# 2_waffling60-MX_matrix.net
KiCad netlist of a schematic drawn in Altium Designer
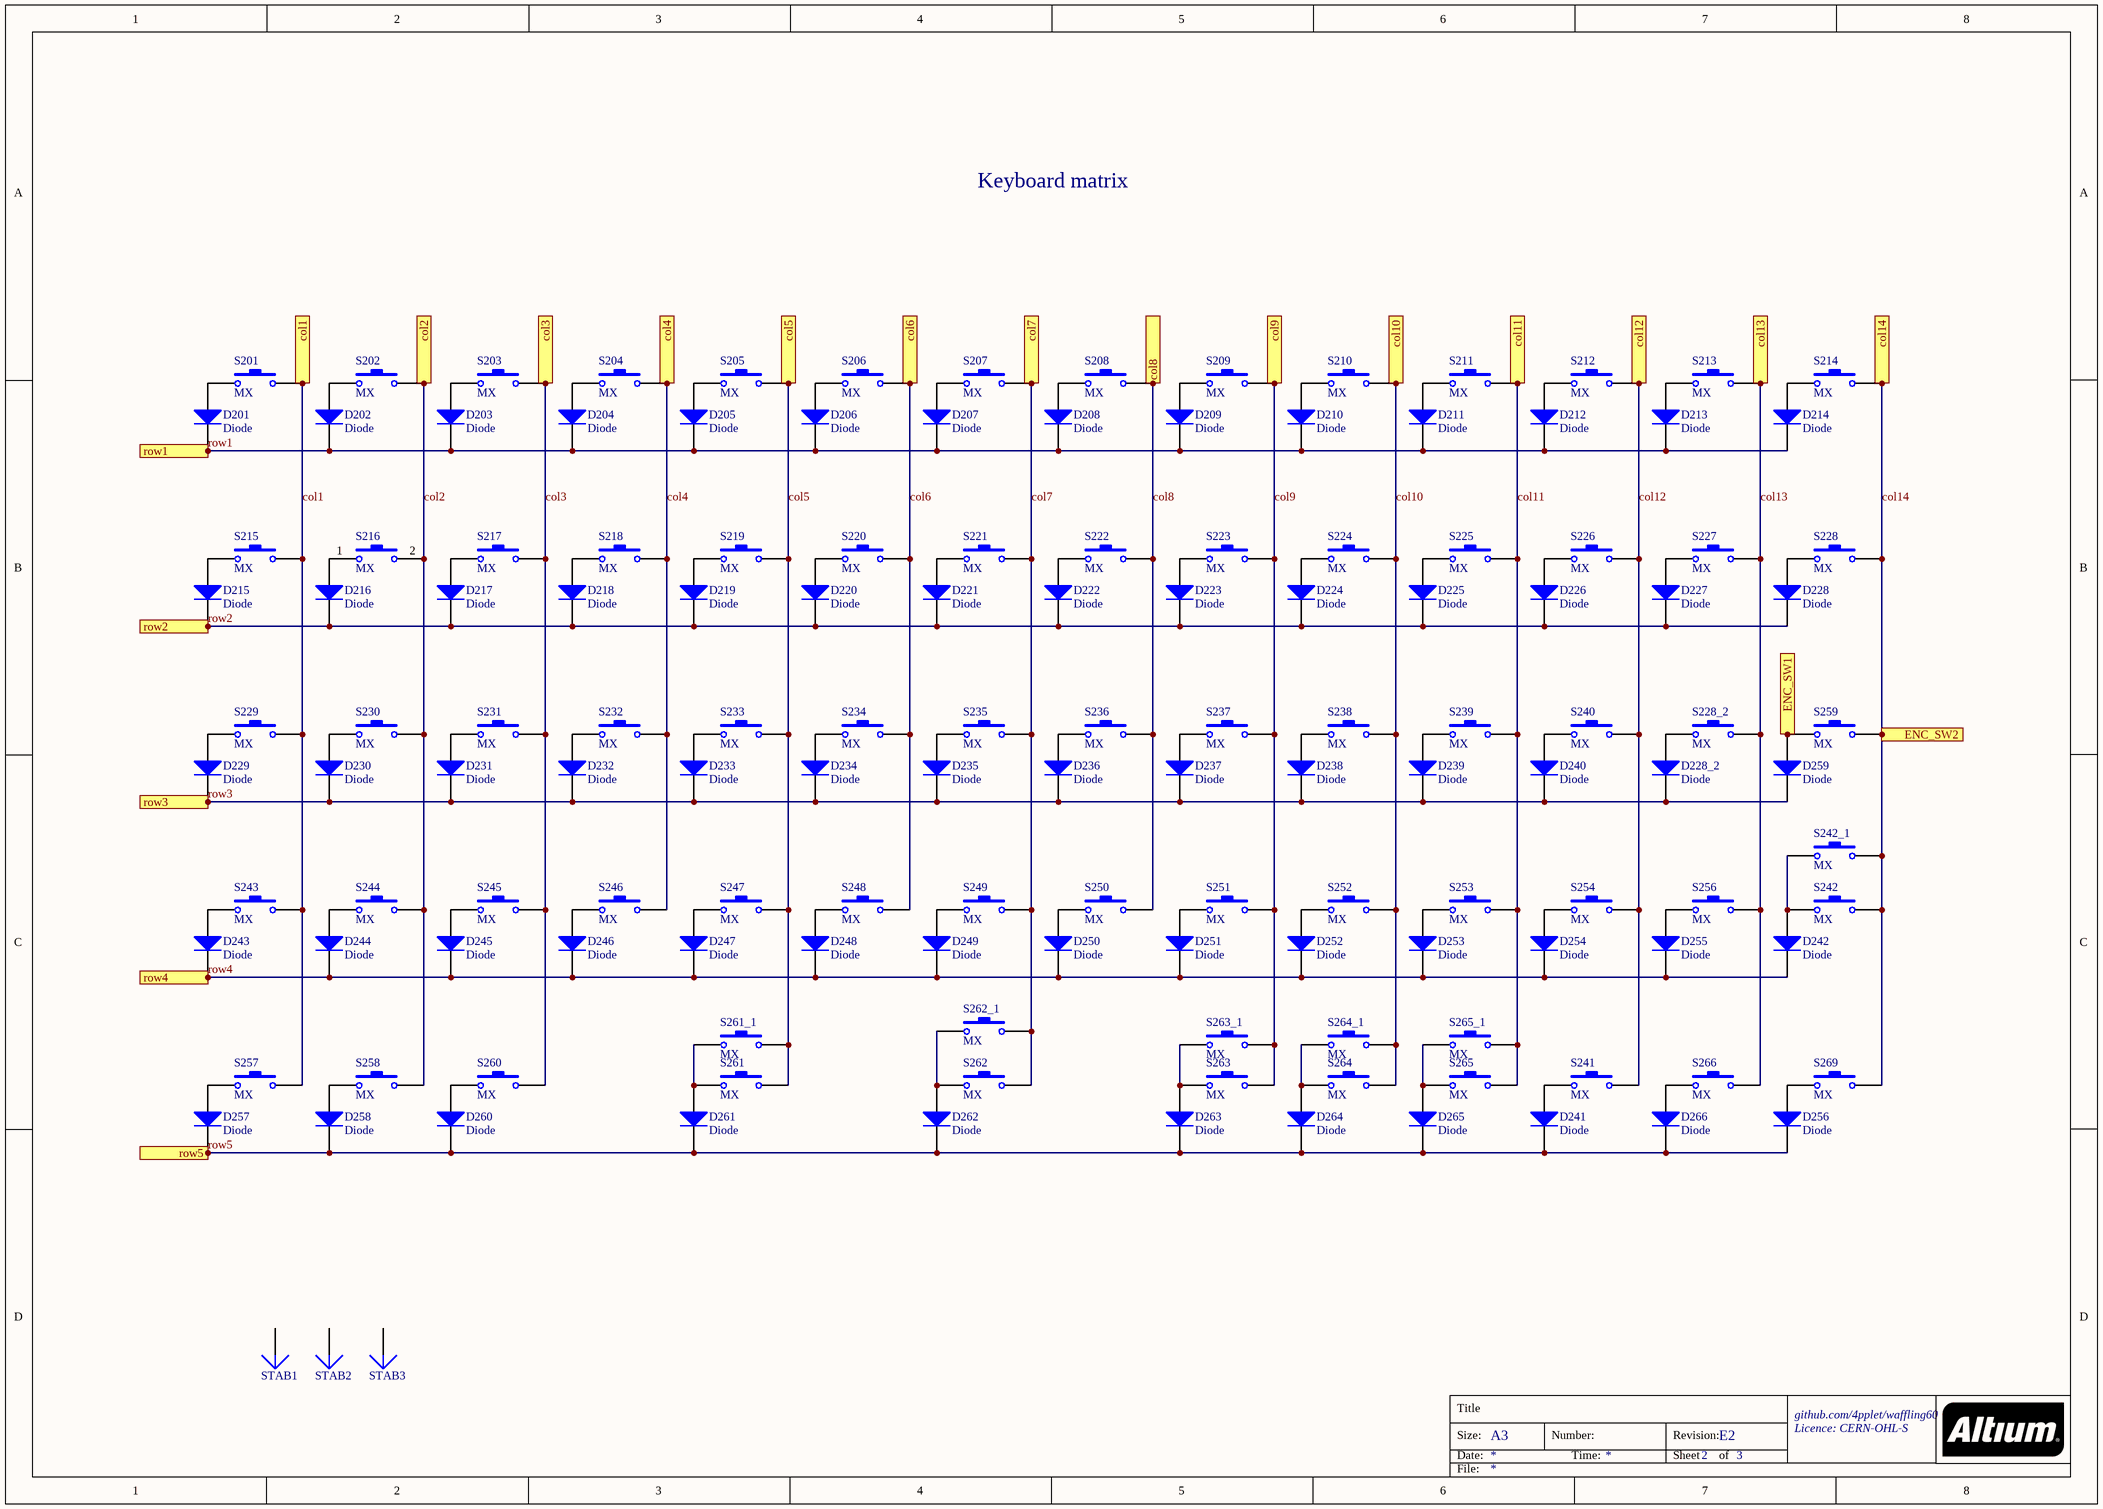
[diagram p0: 2_waffling60-MX_matrix.SchDoc]

(export (version "E")
  (design (tool "Eeschema 10.0.6"))
  (components
    (comp (ref "D201")
      (value "Diode")
      (footprint "SOD-123")
      (description "Default Diode")
      (fields (field (name "LCSC PART #") "C81598") (field (name "MRF.PART") "1N4148W"))
      (libsource (lib "Miscellaneous Devices") (part "Diode"))
    )
    (comp (ref "D202")
      (value "Diode")
      (footprint "SOD-123")
      (description "Default Diode")
      (fields (field (name "LCSC PART #") "C81598") (field (name "MRF.PART") "1N4148W"))
      (libsource (lib "Miscellaneous Devices") (part "Diode"))
    )
    (comp (ref "D203")
      (value "Diode")
      (footprint "SOD-123")
      (description "Default Diode")
      (fields (field (name "LCSC PART #") "C81598") (field (name "MRF.PART") "1N4148W"))
      (libsource (lib "Miscellaneous Devices") (part "Diode"))
    )
    (comp (ref "D204")
      (value "Diode")
      (footprint "SOD-123")
      (description "Default Diode")
      (fields (field (name "LCSC PART #") "C81598") (field (name "MRF.PART") "1N4148W"))
      (libsource (lib "Miscellaneous Devices") (part "Diode"))
    )
    (comp (ref "D205")
      (value "Diode")
      (footprint "SOD-123")
      (description "Default Diode")
      (fields (field (name "LCSC PART #") "C81598") (field (name "MRF.PART") "1N4148W"))
      (libsource (lib "Miscellaneous Devices") (part "Diode"))
    )
    (comp (ref "D206")
      (value "Diode")
      (footprint "SOD-123")
      (description "Default Diode")
      (fields (field (name "LCSC PART #") "C81598") (field (name "MRF.PART") "1N4148W"))
      (libsource (lib "Miscellaneous Devices") (part "Diode"))
    )
    (comp (ref "D207")
      (value "Diode")
      (footprint "SOD-123")
      (description "Default Diode")
      (fields (field (name "LCSC PART #") "C81598") (field (name "MRF.PART") "1N4148W"))
      (libsource (lib "Miscellaneous Devices") (part "Diode"))
    )
    (comp (ref "D208")
      (value "Diode")
      (footprint "SOD-123")
      (description "Default Diode")
      (fields (field (name "LCSC PART #") "C81598") (field (name "MRF.PART") "1N4148W"))
      (libsource (lib "Miscellaneous Devices") (part "Diode"))
    )
    (comp (ref "D209")
      (value "Diode")
      (footprint "SOD-123")
      (description "Default Diode")
      (fields (field (name "LCSC PART #") "C81598") (field (name "MRF.PART") "1N4148W"))
      (libsource (lib "Miscellaneous Devices") (part "Diode"))
    )
    (comp (ref "D210")
      (value "Diode")
      (footprint "SOD-123")
      (description "Default Diode")
      (fields (field (name "LCSC PART #") "C81598") (field (name "MRF.PART") "1N4148W"))
      (libsource (lib "Miscellaneous Devices") (part "Diode"))
    )
    (comp (ref "D211")
      (value "Diode")
      (footprint "SOD-123")
      (description "Default Diode")
      (fields (field (name "LCSC PART #") "C81598") (field (name "MRF.PART") "1N4148W"))
      (libsource (lib "Miscellaneous Devices") (part "Diode"))
    )
    (comp (ref "D212")
      (value "Diode")
      (footprint "SOD-123")
      (description "Default Diode")
      (fields (field (name "LCSC PART #") "C81598") (field (name "MRF.PART") "1N4148W"))
      (libsource (lib "Miscellaneous Devices") (part "Diode"))
    )
    (comp (ref "D213")
      (value "Diode")
      (footprint "SOD-123")
      (description "Default Diode")
      (fields (field (name "LCSC PART #") "C81598") (field (name "MRF.PART") "1N4148W"))
      (libsource (lib "Miscellaneous Devices") (part "Diode"))
    )
    (comp (ref "D214")
      (value "Diode")
      (footprint "SOD-123")
      (description "Default Diode")
      (fields (field (name "LCSC PART #") "C81598") (field (name "MRF.PART") "1N4148W"))
      (libsource (lib "Miscellaneous Devices") (part "Diode"))
    )
    (comp (ref "D215")
      (value "Diode")
      (footprint "SOD-123")
      (description "Default Diode")
      (fields (field (name "LCSC PART #") "C81598") (field (name "MRF.PART") "1N4148W"))
      (libsource (lib "Miscellaneous Devices") (part "Diode"))
    )
    (comp (ref "D216")
      (value "Diode")
      (footprint "SOD-123")
      (description "Default Diode")
      (fields (field (name "LCSC PART #") "C81598") (field (name "MRF.PART") "1N4148W"))
      (libsource (lib "Miscellaneous Devices") (part "Diode"))
    )
    (comp (ref "D217")
      (value "Diode")
      (footprint "SOD-123")
      (description "Default Diode")
      (fields (field (name "LCSC PART #") "C81598") (field (name "MRF.PART") "1N4148W"))
      (libsource (lib "Miscellaneous Devices") (part "Diode"))
    )
    (comp (ref "D218")
      (value "Diode")
      (footprint "SOD-123")
      (description "Default Diode")
      (fields (field (name "LCSC PART #") "C81598") (field (name "MRF.PART") "1N4148W"))
      (libsource (lib "Miscellaneous Devices") (part "Diode"))
    )
    (comp (ref "D219")
      (value "Diode")
      (footprint "SOD-123")
      (description "Default Diode")
      (fields (field (name "LCSC PART #") "C81598") (field (name "MRF.PART") "1N4148W"))
      (libsource (lib "Miscellaneous Devices") (part "Diode"))
    )
    (comp (ref "D220")
      (value "Diode")
      (footprint "SOD-123")
      (description "Default Diode")
      (fields (field (name "LCSC PART #") "C81598") (field (name "MRF.PART") "1N4148W"))
      (libsource (lib "Miscellaneous Devices") (part "Diode"))
    )
    (comp (ref "D221")
      (value "Diode")
      (footprint "SOD-123")
      (description "Default Diode")
      (fields (field (name "LCSC PART #") "C81598") (field (name "MRF.PART") "1N4148W"))
      (libsource (lib "Miscellaneous Devices") (part "Diode"))
    )
    (comp (ref "D222")
      (value "Diode")
      (footprint "SOD-123")
      (description "Default Diode")
      (fields (field (name "LCSC PART #") "C81598") (field (name "MRF.PART") "1N4148W"))
      (libsource (lib "Miscellaneous Devices") (part "Diode"))
    )
    (comp (ref "D223")
      (value "Diode")
      (footprint "SOD-123")
      (description "Default Diode")
      (fields (field (name "LCSC PART #") "C81598") (field (name "MRF.PART") "1N4148W"))
      (libsource (lib "Miscellaneous Devices") (part "Diode"))
    )
    (comp (ref "D224")
      (value "Diode")
      (footprint "SOD-123")
      (description "Default Diode")
      (fields (field (name "LCSC PART #") "C81598") (field (name "MRF.PART") "1N4148W"))
      (libsource (lib "Miscellaneous Devices") (part "Diode"))
    )
    (comp (ref "D225")
      (value "Diode")
      (footprint "SOD-123")
      (description "Default Diode")
      (fields (field (name "LCSC PART #") "C81598") (field (name "MRF.PART") "1N4148W"))
      (libsource (lib "Miscellaneous Devices") (part "Diode"))
    )
    (comp (ref "D226")
      (value "Diode")
      (footprint "SOD-123")
      (description "Default Diode")
      (fields (field (name "LCSC PART #") "C81598") (field (name "MRF.PART") "1N4148W"))
      (libsource (lib "Miscellaneous Devices") (part "Diode"))
    )
    (comp (ref "D227")
      (value "Diode")
      (footprint "SOD-123")
      (description "Default Diode")
      (fields (field (name "LCSC PART #") "C81598") (field (name "MRF.PART") "1N4148W"))
      (libsource (lib "Miscellaneous Devices") (part "Diode"))
    )
    (comp (ref "D228")
      (value "Diode")
      (footprint "SOD-123")
      (description "Default Diode")
      (fields (field (name "LCSC PART #") "C81598") (field (name "MRF.PART") "1N4148W"))
      (libsource (lib "Miscellaneous Devices") (part "Diode"))
    )
    (comp (ref "D228_2")
      (value "Diode")
      (footprint "SOD-123")
      (description "Default Diode")
      (fields (field (name "LCSC PART #") "C81598") (field (name "MRF.PART") "1N4148W"))
      (libsource (lib "Miscellaneous Devices") (part "Diode"))
    )
    (comp (ref "D229")
      (value "Diode")
      (footprint "SOD-123")
      (description "Default Diode")
      (fields (field (name "LCSC PART #") "C81598") (field (name "MRF.PART") "1N4148W"))
      (libsource (lib "Miscellaneous Devices") (part "Diode"))
    )
    (comp (ref "D230")
      (value "Diode")
      (footprint "SOD-123")
      (description "Default Diode")
      (fields (field (name "LCSC PART #") "C81598") (field (name "MRF.PART") "1N4148W"))
      (libsource (lib "Miscellaneous Devices") (part "Diode"))
    )
    (comp (ref "D231")
      (value "Diode")
      (footprint "SOD-123")
      (description "Default Diode")
      (fields (field (name "LCSC PART #") "C81598") (field (name "MRF.PART") "1N4148W"))
      (libsource (lib "Miscellaneous Devices") (part "Diode"))
    )
    (comp (ref "D232")
      (value "Diode")
      (footprint "SOD-123")
      (description "Default Diode")
      (fields (field (name "LCSC PART #") "C81598") (field (name "MRF.PART") "1N4148W"))
      (libsource (lib "Miscellaneous Devices") (part "Diode"))
    )
    (comp (ref "D233")
      (value "Diode")
      (footprint "SOD-123")
      (description "Default Diode")
      (fields (field (name "LCSC PART #") "C81598") (field (name "MRF.PART") "1N4148W"))
      (libsource (lib "Miscellaneous Devices") (part "Diode"))
    )
    (comp (ref "D234")
      (value "Diode")
      (footprint "SOD-123")
      (description "Default Diode")
      (fields (field (name "LCSC PART #") "C81598") (field (name "MRF.PART") "1N4148W"))
      (libsource (lib "Miscellaneous Devices") (part "Diode"))
    )
    (comp (ref "D235")
      (value "Diode")
      (footprint "SOD-123")
      (description "Default Diode")
      (fields (field (name "LCSC PART #") "C81598") (field (name "MRF.PART") "1N4148W"))
      (libsource (lib "Miscellaneous Devices") (part "Diode"))
    )
    (comp (ref "D236")
      (value "Diode")
      (footprint "SOD-123")
      (description "Default Diode")
      (fields (field (name "LCSC PART #") "C81598") (field (name "MRF.PART") "1N4148W"))
      (libsource (lib "Miscellaneous Devices") (part "Diode"))
    )
    (comp (ref "D237")
      (value "Diode")
      (footprint "SOD-123")
      (description "Default Diode")
      (fields (field (name "LCSC PART #") "C81598") (field (name "MRF.PART") "1N4148W"))
      (libsource (lib "Miscellaneous Devices") (part "Diode"))
    )
    (comp (ref "D238")
      (value "Diode")
      (footprint "SOD-123")
      (description "Default Diode")
      (fields (field (name "LCSC PART #") "C81598") (field (name "MRF.PART") "1N4148W"))
      (libsource (lib "Miscellaneous Devices") (part "Diode"))
    )
    (comp (ref "D239")
      (value "Diode")
      (footprint "SOD-123")
      (description "Default Diode")
      (fields (field (name "LCSC PART #") "C81598") (field (name "MRF.PART") "1N4148W"))
      (libsource (lib "Miscellaneous Devices") (part "Diode"))
    )
    (comp (ref "D240")
      (value "Diode")
      (footprint "SOD-123")
      (description "Default Diode")
      (fields (field (name "LCSC PART #") "C81598") (field (name "MRF.PART") "1N4148W"))
      (libsource (lib "Miscellaneous Devices") (part "Diode"))
    )
    (comp (ref "D241")
      (value "Diode")
      (footprint "SOD-123")
      (description "Default Diode")
      (fields (field (name "LCSC PART #") "C81598") (field (name "MRF.PART") "1N4148W"))
      (libsource (lib "Miscellaneous Devices") (part "Diode"))
    )
    (comp (ref "D242")
      (value "Diode")
      (footprint "SOD-123")
      (description "Default Diode")
      (fields (field (name "LCSC PART #") "C81598") (field (name "MRF.PART") "1N4148W"))
      (libsource (lib "Miscellaneous Devices") (part "Diode"))
    )
    (comp (ref "D243")
      (value "Diode")
      (footprint "SOD-123")
      (description "Default Diode")
      (fields (field (name "LCSC PART #") "C81598") (field (name "MRF.PART") "1N4148W"))
      (libsource (lib "Miscellaneous Devices") (part "Diode"))
    )
    (comp (ref "D244")
      (value "Diode")
      (footprint "SOD-123")
      (description "Default Diode")
      (fields (field (name "LCSC PART #") "C81598") (field (name "MRF.PART") "1N4148W"))
      (libsource (lib "Miscellaneous Devices") (part "Diode"))
    )
    (comp (ref "D245")
      (value "Diode")
      (footprint "SOD-123")
      (description "Default Diode")
      (fields (field (name "LCSC PART #") "C81598") (field (name "MRF.PART") "1N4148W"))
      (libsource (lib "Miscellaneous Devices") (part "Diode"))
    )
    (comp (ref "D246")
      (value "Diode")
      (footprint "SOD-123")
      (description "Default Diode")
      (fields (field (name "LCSC PART #") "C81598") (field (name "MRF.PART") "1N4148W"))
      (libsource (lib "Miscellaneous Devices") (part "Diode"))
    )
    (comp (ref "D247")
      (value "Diode")
      (footprint "SOD-123")
      (description "Default Diode")
      (fields (field (name "LCSC PART #") "C81598") (field (name "MRF.PART") "1N4148W"))
      (libsource (lib "Miscellaneous Devices") (part "Diode"))
    )
    (comp (ref "D248")
      (value "Diode")
      (footprint "SOD-123")
      (description "Default Diode")
      (fields (field (name "LCSC PART #") "C81598") (field (name "MRF.PART") "1N4148W"))
      (libsource (lib "Miscellaneous Devices") (part "Diode"))
    )
    (comp (ref "D249")
      (value "Diode")
      (footprint "SOD-123")
      (description "Default Diode")
      (fields (field (name "LCSC PART #") "C81598") (field (name "MRF.PART") "1N4148W"))
      (libsource (lib "Miscellaneous Devices") (part "Diode"))
    )
    (comp (ref "D250")
      (value "Diode")
      (footprint "SOD-123")
      (description "Default Diode")
      (fields (field (name "LCSC PART #") "C81598") (field (name "MRF.PART") "1N4148W"))
      (libsource (lib "Miscellaneous Devices") (part "Diode"))
    )
    (comp (ref "D251")
      (value "Diode")
      (footprint "SOD-123")
      (description "Default Diode")
      (fields (field (name "LCSC PART #") "C81598") (field (name "MRF.PART") "1N4148W"))
      (libsource (lib "Miscellaneous Devices") (part "Diode"))
    )
    (comp (ref "D252")
      (value "Diode")
      (footprint "SOD-123")
      (description "Default Diode")
      (fields (field (name "LCSC PART #") "C81598") (field (name "MRF.PART") "1N4148W"))
      (libsource (lib "Miscellaneous Devices") (part "Diode"))
    )
    (comp (ref "D253")
      (value "Diode")
      (footprint "SOD-123")
      (description "Default Diode")
      (fields (field (name "LCSC PART #") "C81598") (field (name "MRF.PART") "1N4148W"))
      (libsource (lib "Miscellaneous Devices") (part "Diode"))
    )
    (comp (ref "D254")
      (value "Diode")
      (footprint "SOD-123")
      (description "Default Diode")
      (fields (field (name "LCSC PART #") "C81598") (field (name "MRF.PART") "1N4148W"))
      (libsource (lib "Miscellaneous Devices") (part "Diode"))
    )
    (comp (ref "D255")
      (value "Diode")
      (footprint "SOD-123")
      (description "Default Diode")
      (fields (field (name "LCSC PART #") "C81598") (field (name "MRF.PART") "1N4148W"))
      (libsource (lib "Miscellaneous Devices") (part "Diode"))
    )
    (comp (ref "D256")
      (value "Diode")
      (footprint "SOD-123")
      (description "Default Diode")
      (fields (field (name "LCSC PART #") "C81598") (field (name "MRF.PART") "1N4148W"))
      (libsource (lib "Miscellaneous Devices") (part "Diode"))
    )
    (comp (ref "D257")
      (value "Diode")
      (footprint "SOD-123")
      (description "Default Diode")
      (fields (field (name "LCSC PART #") "C81598") (field (name "MRF.PART") "1N4148W"))
      (libsource (lib "Miscellaneous Devices") (part "Diode"))
    )
    (comp (ref "D258")
      (value "Diode")
      (footprint "SOD-123")
      (description "Default Diode")
      (fields (field (name "LCSC PART #") "C81598") (field (name "MRF.PART") "1N4148W"))
      (libsource (lib "Miscellaneous Devices") (part "Diode"))
    )
    (comp (ref "D259")
      (value "Diode")
      (footprint "SOD-123")
      (description "Default Diode")
      (fields (field (name "LCSC PART #") "C81598") (field (name "MRF.PART") "1N4148W"))
      (libsource (lib "Miscellaneous Devices") (part "Diode"))
    )
    (comp (ref "D260")
      (value "Diode")
      (footprint "SOD-123")
      (description "Default Diode")
      (fields (field (name "LCSC PART #") "C81598") (field (name "MRF.PART") "1N4148W"))
      (libsource (lib "Miscellaneous Devices") (part "Diode"))
    )
    (comp (ref "D261")
      (value "Diode")
      (footprint "SOD-123")
      (description "Default Diode")
      (fields (field (name "LCSC PART #") "C81598") (field (name "MRF.PART") "1N4148W"))
      (libsource (lib "Miscellaneous Devices") (part "Diode"))
    )
    (comp (ref "D262")
      (value "Diode")
      (footprint "SOD-123")
      (description "Default Diode")
      (fields (field (name "LCSC PART #") "C81598") (field (name "MRF.PART") "1N4148W"))
      (libsource (lib "Miscellaneous Devices") (part "Diode"))
    )
    (comp (ref "D263")
      (value "Diode")
      (footprint "SOD-123")
      (description "Default Diode")
      (fields (field (name "LCSC PART #") "C81598") (field (name "MRF.PART") "1N4148W"))
      (libsource (lib "Miscellaneous Devices") (part "Diode"))
    )
    (comp (ref "D264")
      (value "Diode")
      (footprint "SOD-123")
      (description "Default Diode")
      (fields (field (name "LCSC PART #") "C81598") (field (name "MRF.PART") "1N4148W"))
      (libsource (lib "Miscellaneous Devices") (part "Diode"))
    )
    (comp (ref "D265")
      (value "Diode")
      (footprint "SOD-123")
      (description "Default Diode")
      (fields (field (name "LCSC PART #") "C81598") (field (name "MRF.PART") "1N4148W"))
      (libsource (lib "Miscellaneous Devices") (part "Diode"))
    )
    (comp (ref "D266")
      (value "Diode")
      (footprint "SOD-123")
      (description "Default Diode")
      (fields (field (name "LCSC PART #") "C81598") (field (name "MRF.PART") "1N4148W"))
      (libsource (lib "Miscellaneous Devices") (part "Diode"))
    )
    (comp (ref "S201")
      (value "MX")
      (footprint "MX-switch - switched pol")
      (description "Switch")
      (libsource (lib "Miscellaneous Devices") (part "SW-PB"))
    )
    (comp (ref "S202")
      (value "MX")
      (footprint "MX-switch")
      (description "Switch")
      (libsource (lib "Miscellaneous Devices") (part "SW-PB"))
    )
    (comp (ref "S203")
      (value "MX")
      (footprint "MX-switch - switched pol")
      (description "Switch")
      (libsource (lib "Miscellaneous Devices") (part "SW-PB"))
    )
    (comp (ref "S204")
      (value "MX")
      (footprint "MX-switch - switched pol")
      (description "Switch")
      (libsource (lib "Miscellaneous Devices") (part "SW-PB"))
    )
    (comp (ref "S205")
      (value "MX")
      (footprint "MX-switch - switched pol")
      (description "Switch")
      (libsource (lib "Miscellaneous Devices") (part "SW-PB"))
    )
    (comp (ref "S206")
      (value "MX")
      (footprint "MX-switch - switched pol")
      (description "Switch")
      (libsource (lib "Miscellaneous Devices") (part "SW-PB"))
    )
    (comp (ref "S207")
      (value "MX")
      (footprint "MX-switch - switched pol")
      (description "Switch")
      (libsource (lib "Miscellaneous Devices") (part "SW-PB"))
    )
    (comp (ref "S208")
      (value "MX")
      (footprint "MX-switch - switched pol")
      (description "Switch")
      (libsource (lib "Miscellaneous Devices") (part "SW-PB"))
    )
    (comp (ref "S209")
      (value "MX")
      (footprint "MX-switch - switched pol")
      (description "Switch")
      (libsource (lib "Miscellaneous Devices") (part "SW-PB"))
    )
    (comp (ref "S210")
      (value "MX")
      (footprint "MX-switch - switched pol")
      (description "Switch")
      (libsource (lib "Miscellaneous Devices") (part "SW-PB"))
    )
    (comp (ref "S211")
      (value "MX")
      (footprint "MX-switch - switched pol")
      (description "Switch")
      (libsource (lib "Miscellaneous Devices") (part "SW-PB"))
    )
    (comp (ref "S212")
      (value "MX")
      (footprint "MX-switch - switched pol")
      (description "Switch")
      (libsource (lib "Miscellaneous Devices") (part "SW-PB"))
    )
    (comp (ref "S213")
      (value "MX")
      (footprint "MX-switch - switched pol")
      (description "Switch")
      (libsource (lib "Miscellaneous Devices") (part "SW-PB"))
    )
    (comp (ref "S214")
      (value "MX")
      (footprint "MX-switch")
      (description "Switch")
      (libsource (lib "Miscellaneous Devices") (part "SW-PB"))
    )
    (comp (ref "S215")
      (value "MX")
      (footprint "MX-switch - switched pol")
      (description "TAB")
      (libsource (lib "Miscellaneous Devices") (part "SW-PB"))
    )
    (comp (ref "S216")
      (value "MX")
      (footprint "MX-switch")
      (description "Switch")
      (libsource (lib "") (part "SW-PB_1"))
    )
    (comp (ref "S217")
      (value "MX")
      (footprint "MX-switch - switched pol")
      (description "Switch")
      (libsource (lib "Miscellaneous Devices") (part "SW-PB"))
    )
    (comp (ref "S218")
      (value "MX")
      (footprint "MX-switch - switched pol")
      (description "Switch")
      (libsource (lib "Miscellaneous Devices") (part "SW-PB"))
    )
    (comp (ref "S219")
      (value "MX")
      (footprint "MX-switch - switched pol")
      (description "Switch")
      (libsource (lib "Miscellaneous Devices") (part "SW-PB"))
    )
    (comp (ref "S220")
      (value "MX")
      (footprint "MX-switch")
      (description "Switch")
      (libsource (lib "Miscellaneous Devices") (part "SW-PB"))
    )
    (comp (ref "S221")
      (value "MX")
      (footprint "MX-switch - switched pol")
      (description "Switch")
      (libsource (lib "Miscellaneous Devices") (part "SW-PB"))
    )
    (comp (ref "S222")
      (value "MX")
      (footprint "MX-switch")
      (description "Switch")
      (libsource (lib "Miscellaneous Devices") (part "SW-PB"))
    )
    (comp (ref "S223")
      (value "MX")
      (footprint "MX-switch - switched pol")
      (description "Switch")
      (libsource (lib "Miscellaneous Devices") (part "SW-PB"))
    )
    (comp (ref "S224")
      (value "MX")
      (footprint "MX-switch - switched pol")
      (description "Switch")
      (libsource (lib "Miscellaneous Devices") (part "SW-PB"))
    )
    (comp (ref "S225")
      (value "MX")
      (footprint "MX-switch - switched pol")
      (description "Switch")
      (libsource (lib "Miscellaneous Devices") (part "SW-PB"))
    )
    (comp (ref "S226")
      (value "MX")
      (footprint "MX-switch")
      (description "Switch")
      (libsource (lib "Miscellaneous Devices") (part "SW-PB"))
    )
    (comp (ref "S227")
      (value "MX")
      (footprint "MX-switch")
      (description "Switch")
      (libsource (lib "Miscellaneous Devices") (part "SW-PB"))
    )
    (comp (ref "S228")
      (value "MX")
      (footprint "MX-switch - 1.5U")
      (description "Switch")
      (libsource (lib "Miscellaneous Devices") (part "SW-PB"))
    )
    (comp (ref "S228_2")
      (value "MX")
      (footprint "MX-switch")
      (description "Switch")
      (libsource (lib "Miscellaneous Devices") (part "SW-PB"))
    )
    (comp (ref "S229")
      (value "MX")
      (footprint "MX-switch - CAPS")
      (description "Switch")
      (libsource (lib "Miscellaneous Devices") (part "SW-PB"))
    )
    (comp (ref "S230")
      (value "MX")
      (footprint "MX-switch")
      (description "Switch")
      (libsource (lib "Miscellaneous Devices") (part "SW-PB"))
    )
    (comp (ref "S231")
      (value "MX")
      (footprint "MX-switch - switched pol")
      (description "Switch")
      (libsource (lib "Miscellaneous Devices") (part "SW-PB"))
    )
    (comp (ref "S232")
      (value "MX")
      (footprint "MX-switch - switched pol")
      (description "Switch")
      (libsource (lib "Miscellaneous Devices") (part "SW-PB"))
    )
    (comp (ref "S233")
      (value "MX")
      (footprint "MX-switch - switched pol")
      (description "Switch")
      (libsource (lib "Miscellaneous Devices") (part "SW-PB"))
    )
    (comp (ref "S234")
      (value "MX")
      (footprint "MX-switch - switched pol")
      (description "Switch")
      (libsource (lib "Miscellaneous Devices") (part "SW-PB"))
    )
    (comp (ref "S235")
      (value "MX")
      (footprint "MX-switch - switched pol")
      (description "Switch")
      (libsource (lib "Miscellaneous Devices") (part "SW-PB"))
    )
    (comp (ref "S236")
      (value "MX")
      (footprint "MX-switch - switched pol")
      (description "Switch")
      (libsource (lib "Miscellaneous Devices") (part "SW-PB"))
    )
    (comp (ref "S237")
      (value "MX")
      (footprint "MX-switch - switched pol")
      (description "Switch")
      (libsource (lib "Miscellaneous Devices") (part "SW-PB"))
    )
    (comp (ref "S238")
      (value "MX")
      (footprint "MX-switch - switched pol")
      (description "Switch")
      (libsource (lib "Miscellaneous Devices") (part "SW-PB"))
    )
    (comp (ref "S239")
      (value "MX")
      (footprint "MX-switch - switched pol")
      (description "Switch")
      (libsource (lib "Miscellaneous Devices") (part "SW-PB"))
    )
    (comp (ref "S240")
      (value "MX")
      (footprint "MX-switch - switched pol")
      (description "Switch")
      (libsource (lib "Miscellaneous Devices") (part "SW-PB"))
    )
    (comp (ref "S241")
      (value "MX")
      (footprint "MX-switch - 1u MOD-R")
      (description "Switch")
      (libsource (lib "Miscellaneous Devices") (part "SW-PB"))
    )
    (comp (ref "S242")
      (value "MX")
      (footprint "MX-switch - switched pol")
      (description "Switch")
      (libsource (lib "Miscellaneous Devices") (part "SW-PB"))
    )
    (comp (ref "S242_1")
      (value "MX")
      (footprint "MX-switch - switched pol")
      (description "Switch")
      (libsource (lib "Miscellaneous Devices") (part "SW-PB"))
    )
    (comp (ref "S243")
      (value "MX")
      (footprint "MX-switch - Left shift")
      (description "Switch")
      (libsource (lib "Miscellaneous Devices") (part "SW-PB"))
    )
    (comp (ref "S244")
      (value "MX")
      (footprint "MX-switch")
      (description "Switch")
      (libsource (lib "Miscellaneous Devices") (part "SW-PB"))
    )
    (comp (ref "S245")
      (value "MX")
      (footprint "MX-switch - switched pol")
      (description "Switch")
      (libsource (lib "Miscellaneous Devices") (part "SW-PB"))
    )
    (comp (ref "S246")
      (value "MX")
      (footprint "MX-switch - switched pol")
      (description "Switch")
      (libsource (lib "Miscellaneous Devices") (part "SW-PB"))
    )
    (comp (ref "S247")
      (value "MX")
      (footprint "MX-switch - switched pol")
      (description "Switch")
      (libsource (lib "Miscellaneous Devices") (part "SW-PB"))
    )
    (comp (ref "S248")
      (value "MX")
      (footprint "MX-switch - switched pol")
      (description "Switch")
      (libsource (lib "Miscellaneous Devices") (part "SW-PB"))
    )
    (comp (ref "S249")
      (value "MX")
      (footprint "MX-switch - switched pol")
      (description "Switch")
      (libsource (lib "Miscellaneous Devices") (part "SW-PB"))
    )
    (comp (ref "S250")
      (value "MX")
      (footprint "MX-switch - switched pol")
      (description "Switch")
      (libsource (lib "Miscellaneous Devices") (part "SW-PB"))
    )
    (comp (ref "S251")
      (value "MX")
      (footprint "MX-switch - switched pol")
      (description "Switch")
      (libsource (lib "Miscellaneous Devices") (part "SW-PB"))
    )
    (comp (ref "S252")
      (value "MX")
      (footprint "MX-switch - switched pol")
      (description "Switch")
      (libsource (lib "Miscellaneous Devices") (part "SW-PB"))
    )
    (comp (ref "S253")
      (value "MX")
      (footprint "MX-switch - switched pol")
      (description "Switch")
      (libsource (lib "Miscellaneous Devices") (part "SW-PB"))
    )
    (comp (ref "S254")
      (value "MX")
      (footprint "MX-switch - switched pol")
      (description "Switch")
      (libsource (lib "Miscellaneous Devices") (part "SW-PB"))
    )
    (comp (ref "S256")
      (value "MX")
      (footprint "MX-switch - right shift")
      (description "Switch")
      (libsource (lib "Miscellaneous Devices") (part "SW-PB"))
    )
    (comp (ref "S257")
      (value "MX")
      (footprint "MX-switch - 1.5u MOD-L")
      (description "Switch")
      (libsource (lib "Miscellaneous Devices") (part "SW-PB"))
    )
    (comp (ref "S258")
      (value "MX")
      (footprint "MX-switch - 1u MOD-L")
      (description "Switch")
      (libsource (lib "Miscellaneous Devices") (part "SW-PB"))
    )
    (comp (ref "S259")
      (value "MX")
      (footprint "MX-switch - backspace")
      (description "Switch")
      (libsource (lib "Miscellaneous Devices") (part "SW-PB"))
    )
    (comp (ref "S260")
      (value "MX")
      (footprint "MX-switch - 1.5u MOD-L")
      (description "Switch")
      (libsource (lib "Miscellaneous Devices") (part "SW-PB"))
    )
    (comp (ref "S261")
      (value "MX")
      (footprint "MX-SWITCH - L SPLIT SPACE_V2")
      (description "Switch")
      (libsource (lib "Miscellaneous Devices") (part "SW-PB"))
    )
    (comp (ref "S261_1")
      (value "MX")
      (footprint "MX-switch - 3U - rotated stab")
      (description "Switch")
      (libsource (lib "Miscellaneous Devices") (part "SW-PB"))
    )
    (comp (ref "S262")
      (value "MX")
      (footprint "MX-switch - Space_V3")
      (description "Switch")
      (libsource (lib "Miscellaneous Devices") (part "SW-PB"))
    )
    (comp (ref "S262_1")
      (value "MX")
      (footprint "MX-switch - switched pol")
      (description "Switch")
      (libsource (lib "Miscellaneous Devices") (part "SW-PB"))
    )
    (comp (ref "S263")
      (value "MX")
      (footprint "MX-SWITCH - R SPLIT SPACE_V2")
      (description "Switch")
      (libsource (lib "Miscellaneous Devices") (part "SW-PB"))
    )
    (comp (ref "S263_1")
      (value "MX")
      (footprint "MX-switch - 3U - rotated stab")
      (description "Switch")
      (libsource (lib "Miscellaneous Devices") (part "SW-PB"))
    )
    (comp (ref "S264")
      (value "MX")
      (footprint "MX-switch - switched pol")
      (description "Switch")
      (libsource (lib "Miscellaneous Devices") (part "SW-PB"))
    )
    (comp (ref "S264_1")
      (value "MX")
      (footprint "MX-switch - switched pol")
      (description "Switch")
      (libsource (lib "Miscellaneous Devices") (part "SW-PB"))
    )
    (comp (ref "S265")
      (value "MX")
      (footprint "MX-switch - 1.5u MOD-R")
      (description "Switch")
      (libsource (lib "Miscellaneous Devices") (part "SW-PB"))
    )
    (comp (ref "S265_1")
      (value "MX")
      (footprint "MX-switch - switched pol")
      (description "Switch")
      (libsource (lib "Miscellaneous Devices") (part "SW-PB"))
    )
    (comp (ref "S266")
      (value "MX")
      (footprint "MX-switch - 1.5u MOD-R")
      (description "Switch")
      (libsource (lib "Miscellaneous Devices") (part "SW-PB"))
    )
    (comp (ref "S269")
      (value "MX")
      (footprint "MX-switch")
      (description "Switch")
      (libsource (lib "Miscellaneous Devices") (part "SW-PB"))
    )
    (comp (ref "STAB1")
      (value "Plug")
      (footprint "Stab 10U")
      (libsource (lib "Miscellaneous Connectors") (part "Plug"))
    )
    (comp (ref "STAB2")
      (value "Plug")
      (footprint "Stab 2u")
      (libsource (lib "Miscellaneous Connectors") (part "Plug"))
    )
    (comp (ref "STAB3")
      (value "Plug")
      (footprint "Stab 2u")
      (libsource (lib "Miscellaneous Connectors") (part "Plug"))
    )
  )
  (nets
    (net (code "1") (name "/ENC_SW1") (class "Default")
      (node (ref "D259") (pin "1") (pinfunction "A_1") (pintype "passive"))
      (node (ref "S259") (pin "1") (pinfunction "1_1") (pintype "passive"))
    )
    (net (code "2") (name "/col1") (class "Default")
      (node (ref "S201") (pin "2") (pinfunction "2_2") (pintype "passive"))
      (node (ref "S215") (pin "2") (pinfunction "2_2") (pintype "passive"))
      (node (ref "S229") (pin "1") (pinfunction "1_1") (pintype "passive"))
      (node (ref "S243") (pin "2") (pinfunction "2_2") (pintype "passive"))
      (node (ref "S257") (pin "1") (pinfunction "1_1") (pintype "passive"))
    )
    (net (code "3") (name "/col2") (class "Default")
      (node (ref "S202") (pin "2") (pinfunction "2_2") (pintype "passive"))
      (node (ref "S216") (pin "2") (pinfunction "2_2") (pintype "passive"))
      (node (ref "S230") (pin "2") (pinfunction "2_2") (pintype "passive"))
      (node (ref "S244") (pin "1") (pinfunction "1_1") (pintype "passive"))
      (node (ref "S258") (pin "2") (pinfunction "2_2") (pintype "passive"))
    )
    (net (code "4") (name "/col3") (class "Default")
      (node (ref "S203") (pin "2") (pinfunction "2_2") (pintype "passive"))
      (node (ref "S217") (pin "2") (pinfunction "2_2") (pintype "passive"))
      (node (ref "S231") (pin "2") (pinfunction "2_2") (pintype "passive"))
      (node (ref "S245") (pin "2") (pinfunction "2_2") (pintype "passive"))
      (node (ref "S260") (pin "2") (pinfunction "2_2") (pintype "passive"))
    )
    (net (code "5") (name "/col4") (class "Default")
      (node (ref "S204") (pin "2") (pinfunction "2_2") (pintype "passive"))
      (node (ref "S218") (pin "2") (pinfunction "2_2") (pintype "passive"))
      (node (ref "S232") (pin "2") (pinfunction "2_2") (pintype "passive"))
      (node (ref "S246") (pin "2") (pinfunction "2_2") (pintype "passive"))
    )
    (net (code "6") (name "/col5") (class "Default")
      (node (ref "S205") (pin "2") (pinfunction "2_2") (pintype "passive"))
      (node (ref "S219") (pin "2") (pinfunction "2_2") (pintype "passive"))
      (node (ref "S233") (pin "2") (pinfunction "2_2") (pintype "passive"))
      (node (ref "S247") (pin "2") (pinfunction "2_2") (pintype "passive"))
      (node (ref "S261") (pin "2") (pinfunction "2_2") (pintype "passive"))
      (node (ref "S261_1") (pin "2") (pinfunction "2_2") (pintype "passive"))
    )
    (net (code "7") (name "/col6") (class "Default")
      (node (ref "S206") (pin "2") (pinfunction "2_2") (pintype "passive"))
      (node (ref "S220") (pin "2") (pinfunction "2_2") (pintype "passive"))
      (node (ref "S234") (pin "2") (pinfunction "2_2") (pintype "passive"))
      (node (ref "S248") (pin "2") (pinfunction "2_2") (pintype "passive"))
    )
    (net (code "8") (name "/col7") (class "Default")
      (node (ref "S207") (pin "2") (pinfunction "2_2") (pintype "passive"))
      (node (ref "S221") (pin "2") (pinfunction "2_2") (pintype "passive"))
      (node (ref "S235") (pin "2") (pinfunction "2_2") (pintype "passive"))
      (node (ref "S249") (pin "2") (pinfunction "2_2") (pintype "passive"))
      (node (ref "S262") (pin "1") (pinfunction "1_1") (pintype "passive"))
      (node (ref "S262_1") (pin "1") (pinfunction "1_1") (pintype "passive"))
    )
    (net (code "9") (name "/col8") (class "Default")
      (node (ref "S208") (pin "2") (pinfunction "2_2") (pintype "passive"))
      (node (ref "S222") (pin "2") (pinfunction "2_2") (pintype "passive"))
      (node (ref "S236") (pin "2") (pinfunction "2_2") (pintype "passive"))
      (node (ref "S250") (pin "2") (pinfunction "2_2") (pintype "passive"))
    )
    (net (code "10") (name "/col9") (class "Default")
      (node (ref "S209") (pin "2") (pinfunction "2_2") (pintype "passive"))
      (node (ref "S223") (pin "2") (pinfunction "2_2") (pintype "passive"))
      (node (ref "S237") (pin "2") (pinfunction "2_2") (pintype "passive"))
      (node (ref "S251") (pin "2") (pinfunction "2_2") (pintype "passive"))
      (node (ref "S263") (pin "1") (pinfunction "1_1") (pintype "passive"))
      (node (ref "S263_1") (pin "1") (pinfunction "1_1") (pintype "passive"))
    )
    (net (code "11") (name "/col10") (class "Default")
      (node (ref "S210") (pin "2") (pinfunction "2_2") (pintype "passive"))
      (node (ref "S224") (pin "2") (pinfunction "2_2") (pintype "passive"))
      (node (ref "S238") (pin "2") (pinfunction "2_2") (pintype "passive"))
      (node (ref "S252") (pin "2") (pinfunction "2_2") (pintype "passive"))
      (node (ref "S264") (pin "2") (pinfunction "2_2") (pintype "passive"))
      (node (ref "S264_1") (pin "2") (pinfunction "2_2") (pintype "passive"))
    )
    (net (code "12") (name "/col11") (class "Default")
      (node (ref "S211") (pin "2") (pinfunction "2_2") (pintype "passive"))
      (node (ref "S225") (pin "2") (pinfunction "2_2") (pintype "passive"))
      (node (ref "S239") (pin "2") (pinfunction "2_2") (pintype "passive"))
      (node (ref "S253") (pin "2") (pinfunction "2_2") (pintype "passive"))
      (node (ref "S265") (pin "1") (pinfunction "1_1") (pintype "passive"))
      (node (ref "S265_1") (pin "2") (pinfunction "2_2") (pintype "passive"))
    )
    (net (code "13") (name "/col12") (class "Default")
      (node (ref "S212") (pin "2") (pinfunction "2_2") (pintype "passive"))
      (node (ref "S226") (pin "2") (pinfunction "2_2") (pintype "passive"))
      (node (ref "S240") (pin "2") (pinfunction "2_2") (pintype "passive"))
      (node (ref "S241") (pin "1") (pinfunction "1_1") (pintype "passive"))
      (node (ref "S254") (pin "2") (pinfunction "2_2") (pintype "passive"))
    )
    (net (code "14") (name "/col13") (class "Default")
      (node (ref "S213") (pin "2") (pinfunction "2_2") (pintype "passive"))
      (node (ref "S227") (pin "2") (pinfunction "2_2") (pintype "passive"))
      (node (ref "S228_2") (pin "2") (pinfunction "2_2") (pintype "passive"))
      (node (ref "S256") (pin "2") (pinfunction "2_2") (pintype "passive"))
      (node (ref "S266") (pin "2") (pinfunction "2_2") (pintype "passive"))
    )
    (net (code "15") (name "/col14") (class "Default")
      (node (ref "S214") (pin "2") (pinfunction "2_2") (pintype "passive"))
      (node (ref "S228") (pin "2") (pinfunction "2_2") (pintype "passive"))
      (node (ref "S242") (pin "2") (pinfunction "2_2") (pintype "passive"))
      (node (ref "S242_1") (pin "2") (pinfunction "2_2") (pintype "passive"))
      (node (ref "S259") (pin "2") (pinfunction "2_2") (pintype "passive"))
      (node (ref "S269") (pin "2") (pinfunction "2_2") (pintype "passive"))
    )
    (net (code "16") (name "/row1") (class "Default")
      (node (ref "D201") (pin "2") (pinfunction "K_2") (pintype "passive"))
      (node (ref "D202") (pin "2") (pinfunction "K_2") (pintype "passive"))
      (node (ref "D203") (pin "2") (pinfunction "K_2") (pintype "passive"))
      (node (ref "D204") (pin "2") (pinfunction "K_2") (pintype "passive"))
      (node (ref "D205") (pin "2") (pinfunction "K_2") (pintype "passive"))
      (node (ref "D206") (pin "2") (pinfunction "K_2") (pintype "passive"))
      (node (ref "D207") (pin "2") (pinfunction "K_2") (pintype "passive"))
      (node (ref "D208") (pin "2") (pinfunction "K_2") (pintype "passive"))
      (node (ref "D209") (pin "2") (pinfunction "K_2") (pintype "passive"))
      (node (ref "D210") (pin "2") (pinfunction "K_2") (pintype "passive"))
      (node (ref "D211") (pin "2") (pinfunction "K_2") (pintype "passive"))
      (node (ref "D212") (pin "2") (pinfunction "K_2") (pintype "passive"))
      (node (ref "D213") (pin "2") (pinfunction "K_2") (pintype "passive"))
      (node (ref "D214") (pin "2") (pinfunction "K_2") (pintype "passive"))
    )
    (net (code "17") (name "/row2") (class "Default")
      (node (ref "D215") (pin "2") (pinfunction "K_2") (pintype "passive"))
      (node (ref "D216") (pin "2") (pinfunction "K_2") (pintype "passive"))
      (node (ref "D217") (pin "2") (pinfunction "K_2") (pintype "passive"))
      (node (ref "D218") (pin "2") (pinfunction "K_2") (pintype "passive"))
      (node (ref "D219") (pin "2") (pinfunction "K_2") (pintype "passive"))
      (node (ref "D220") (pin "2") (pinfunction "K_2") (pintype "passive"))
      (node (ref "D221") (pin "2") (pinfunction "K_2") (pintype "passive"))
      (node (ref "D222") (pin "2") (pinfunction "K_2") (pintype "passive"))
      (node (ref "D223") (pin "2") (pinfunction "K_2") (pintype "passive"))
      (node (ref "D224") (pin "2") (pinfunction "K_2") (pintype "passive"))
      (node (ref "D225") (pin "2") (pinfunction "K_2") (pintype "passive"))
      (node (ref "D226") (pin "2") (pinfunction "K_2") (pintype "passive"))
      (node (ref "D227") (pin "2") (pinfunction "K_2") (pintype "passive"))
      (node (ref "D228") (pin "2") (pinfunction "K_2") (pintype "passive"))
    )
    (net (code "18") (name "/row3") (class "Default")
      (node (ref "D228_2") (pin "2") (pinfunction "K_2") (pintype "passive"))
      (node (ref "D229") (pin "2") (pinfunction "K_2") (pintype "passive"))
      (node (ref "D230") (pin "2") (pinfunction "K_2") (pintype "passive"))
      (node (ref "D231") (pin "2") (pinfunction "K_2") (pintype "passive"))
      (node (ref "D232") (pin "2") (pinfunction "K_2") (pintype "passive"))
      (node (ref "D233") (pin "2") (pinfunction "K_2") (pintype "passive"))
      (node (ref "D234") (pin "2") (pinfunction "K_2") (pintype "passive"))
      (node (ref "D235") (pin "2") (pinfunction "K_2") (pintype "passive"))
      (node (ref "D236") (pin "2") (pinfunction "K_2") (pintype "passive"))
      (node (ref "D237") (pin "2") (pinfunction "K_2") (pintype "passive"))
      (node (ref "D238") (pin "2") (pinfunction "K_2") (pintype "passive"))
      (node (ref "D239") (pin "2") (pinfunction "K_2") (pintype "passive"))
      (node (ref "D240") (pin "2") (pinfunction "K_2") (pintype "passive"))
      (node (ref "D259") (pin "2") (pinfunction "K_2") (pintype "passive"))
    )
    (net (code "19") (name "/row4") (class "Default")
      (node (ref "D242") (pin "2") (pinfunction "K_2") (pintype "passive"))
      (node (ref "D243") (pin "2") (pinfunction "K_2") (pintype "passive"))
      (node (ref "D244") (pin "2") (pinfunction "K_2") (pintype "passive"))
      (node (ref "D245") (pin "2") (pinfunction "K_2") (pintype "passive"))
      (node (ref "D246") (pin "2") (pinfunction "K_2") (pintype "passive"))
      (node (ref "D247") (pin "2") (pinfunction "K_2") (pintype "passive"))
      (node (ref "D248") (pin "2") (pinfunction "K_2") (pintype "passive"))
      (node (ref "D249") (pin "2") (pinfunction "K_2") (pintype "passive"))
      (node (ref "D250") (pin "2") (pinfunction "K_2") (pintype "passive"))
      (node (ref "D251") (pin "2") (pinfunction "K_2") (pintype "passive"))
      (node (ref "D252") (pin "2") (pinfunction "K_2") (pintype "passive"))
      (node (ref "D253") (pin "2") (pinfunction "K_2") (pintype "passive"))
      (node (ref "D254") (pin "2") (pinfunction "K_2") (pintype "passive"))
      (node (ref "D255") (pin "2") (pinfunction "K_2") (pintype "passive"))
    )
    (net (code "20") (name "/row5") (class "Default")
      (node (ref "D241") (pin "2") (pinfunction "K_2") (pintype "passive"))
      (node (ref "D256") (pin "2") (pinfunction "K_2") (pintype "passive"))
      (node (ref "D257") (pin "2") (pinfunction "K_2") (pintype "passive"))
      (node (ref "D258") (pin "2") (pinfunction "K_2") (pintype "passive"))
      (node (ref "D260") (pin "2") (pinfunction "K_2") (pintype "passive"))
      (node (ref "D261") (pin "2") (pinfunction "K_2") (pintype "passive"))
      (node (ref "D262") (pin "2") (pinfunction "K_2") (pintype "passive"))
      (node (ref "D263") (pin "2") (pinfunction "K_2") (pintype "passive"))
      (node (ref "D264") (pin "2") (pinfunction "K_2") (pintype "passive"))
      (node (ref "D265") (pin "2") (pinfunction "K_2") (pintype "passive"))
      (node (ref "D266") (pin "2") (pinfunction "K_2") (pintype "passive"))
    )
    (net (code "21") (name "Net-(D201-A)") (class "Default")
      (node (ref "D201") (pin "1") (pinfunction "A_1") (pintype "passive"))
      (node (ref "S201") (pin "1") (pinfunction "1_1") (pintype "passive"))
    )
    (net (code "22") (name "Net-(D202-A)") (class "Default")
      (node (ref "D202") (pin "1") (pinfunction "A_1") (pintype "passive"))
      (node (ref "S202") (pin "1") (pinfunction "1_1") (pintype "passive"))
    )
    (net (code "23") (name "Net-(D203-A)") (class "Default")
      (node (ref "D203") (pin "1") (pinfunction "A_1") (pintype "passive"))
      (node (ref "S203") (pin "1") (pinfunction "1_1") (pintype "passive"))
    )
    (net (code "24") (name "Net-(D204-A)") (class "Default")
      (node (ref "D204") (pin "1") (pinfunction "A_1") (pintype "passive"))
      (node (ref "S204") (pin "1") (pinfunction "1_1") (pintype "passive"))
    )
    (net (code "25") (name "Net-(D205-A)") (class "Default")
      (node (ref "D205") (pin "1") (pinfunction "A_1") (pintype "passive"))
      (node (ref "S205") (pin "1") (pinfunction "1_1") (pintype "passive"))
    )
    (net (code "26") (name "Net-(D206-A)") (class "Default")
      (node (ref "D206") (pin "1") (pinfunction "A_1") (pintype "passive"))
      (node (ref "S206") (pin "1") (pinfunction "1_1") (pintype "passive"))
    )
    (net (code "27") (name "Net-(D207-A)") (class "Default")
      (node (ref "D207") (pin "1") (pinfunction "A_1") (pintype "passive"))
      (node (ref "S207") (pin "1") (pinfunction "1_1") (pintype "passive"))
    )
    (net (code "28") (name "Net-(D208-A)") (class "Default")
      (node (ref "D208") (pin "1") (pinfunction "A_1") (pintype "passive"))
      (node (ref "S208") (pin "1") (pinfunction "1_1") (pintype "passive"))
    )
    (net (code "29") (name "Net-(D209-A)") (class "Default")
      (node (ref "D209") (pin "1") (pinfunction "A_1") (pintype "passive"))
      (node (ref "S209") (pin "1") (pinfunction "1_1") (pintype "passive"))
    )
    (net (code "30") (name "Net-(D210-A)") (class "Default")
      (node (ref "D210") (pin "1") (pinfunction "A_1") (pintype "passive"))
      (node (ref "S210") (pin "1") (pinfunction "1_1") (pintype "passive"))
    )
    (net (code "31") (name "Net-(D211-A)") (class "Default")
      (node (ref "D211") (pin "1") (pinfunction "A_1") (pintype "passive"))
      (node (ref "S211") (pin "1") (pinfunction "1_1") (pintype "passive"))
    )
    (net (code "32") (name "Net-(D212-A)") (class "Default")
      (node (ref "D212") (pin "1") (pinfunction "A_1") (pintype "passive"))
      (node (ref "S212") (pin "1") (pinfunction "1_1") (pintype "passive"))
    )
    (net (code "33") (name "Net-(D213-A)") (class "Default")
      (node (ref "D213") (pin "1") (pinfunction "A_1") (pintype "passive"))
      (node (ref "S213") (pin "1") (pinfunction "1_1") (pintype "passive"))
    )
    (net (code "34") (name "Net-(D214-A)") (class "Default")
      (node (ref "D214") (pin "1") (pinfunction "A_1") (pintype "passive"))
      (node (ref "S214") (pin "1") (pinfunction "1_1") (pintype "passive"))
    )
    (net (code "35") (name "Net-(D215-A)") (class "Default")
      (node (ref "D215") (pin "1") (pinfunction "A_1") (pintype "passive"))
      (node (ref "S215") (pin "1") (pinfunction "1_1") (pintype "passive"))
    )
    (net (code "36") (name "Net-(D216-A)") (class "Default")
      (node (ref "D216") (pin "1") (pinfunction "A_1") (pintype "passive"))
      (node (ref "S216") (pin "1") (pinfunction "1_1") (pintype "passive"))
    )
    (net (code "37") (name "Net-(D217-A)") (class "Default")
      (node (ref "D217") (pin "1") (pinfunction "A_1") (pintype "passive"))
      (node (ref "S217") (pin "1") (pinfunction "1_1") (pintype "passive"))
    )
    (net (code "38") (name "Net-(D218-A)") (class "Default")
      (node (ref "D218") (pin "1") (pinfunction "A_1") (pintype "passive"))
      (node (ref "S218") (pin "1") (pinfunction "1_1") (pintype "passive"))
    )
    (net (code "39") (name "Net-(D219-A)") (class "Default")
      (node (ref "D219") (pin "1") (pinfunction "A_1") (pintype "passive"))
      (node (ref "S219") (pin "1") (pinfunction "1_1") (pintype "passive"))
    )
    (net (code "40") (name "Net-(D220-A)") (class "Default")
      (node (ref "D220") (pin "1") (pinfunction "A_1") (pintype "passive"))
      (node (ref "S220") (pin "1") (pinfunction "1_1") (pintype "passive"))
    )
    (net (code "41") (name "Net-(D221-A)") (class "Default")
      (node (ref "D221") (pin "1") (pinfunction "A_1") (pintype "passive"))
      (node (ref "S221") (pin "1") (pinfunction "1_1") (pintype "passive"))
    )
    (net (code "42") (name "Net-(D222-A)") (class "Default")
      (node (ref "D222") (pin "1") (pinfunction "A_1") (pintype "passive"))
      (node (ref "S222") (pin "1") (pinfunction "1_1") (pintype "passive"))
    )
    (net (code "43") (name "Net-(D223-A)") (class "Default")
      (node (ref "D223") (pin "1") (pinfunction "A_1") (pintype "passive"))
      (node (ref "S223") (pin "1") (pinfunction "1_1") (pintype "passive"))
    )
    (net (code "44") (name "Net-(D224-A)") (class "Default")
      (node (ref "D224") (pin "1") (pinfunction "A_1") (pintype "passive"))
      (node (ref "S224") (pin "1") (pinfunction "1_1") (pintype "passive"))
    )
    (net (code "45") (name "Net-(D225-A)") (class "Default")
      (node (ref "D225") (pin "1") (pinfunction "A_1") (pintype "passive"))
      (node (ref "S225") (pin "1") (pinfunction "1_1") (pintype "passive"))
    )
    (net (code "46") (name "Net-(D226-A)") (class "Default")
      (node (ref "D226") (pin "1") (pinfunction "A_1") (pintype "passive"))
      (node (ref "S226") (pin "1") (pinfunction "1_1") (pintype "passive"))
    )
    (net (code "47") (name "Net-(D227-A)") (class "Default")
      (node (ref "D227") (pin "1") (pinfunction "A_1") (pintype "passive"))
      (node (ref "S227") (pin "1") (pinfunction "1_1") (pintype "passive"))
    )
    (net (code "48") (name "Net-(D228-A)") (class "Default")
      (node (ref "D228") (pin "1") (pinfunction "A_1") (pintype "passive"))
      (node (ref "S228") (pin "1") (pinfunction "1_1") (pintype "passive"))
    )
    (net (code "49") (name "Net-(D228_2-A)") (class "Default")
      (node (ref "D228_2") (pin "1") (pinfunction "A_1") (pintype "passive"))
      (node (ref "S228_2") (pin "1") (pinfunction "1_1") (pintype "passive"))
    )
    (net (code "50") (name "Net-(D229-A)") (class "Default")
      (node (ref "D229") (pin "1") (pinfunction "A_1") (pintype "passive"))
      (node (ref "S229") (pin "2") (pinfunction "2_2") (pintype "passive"))
    )
    (net (code "51") (name "Net-(D230-A)") (class "Default")
      (node (ref "D230") (pin "1") (pinfunction "A_1") (pintype "passive"))
      (node (ref "S230") (pin "1") (pinfunction "1_1") (pintype "passive"))
    )
    (net (code "52") (name "Net-(D231-A)") (class "Default")
      (node (ref "D231") (pin "1") (pinfunction "A_1") (pintype "passive"))
      (node (ref "S231") (pin "1") (pinfunction "1_1") (pintype "passive"))
    )
    (net (code "53") (name "Net-(D232-A)") (class "Default")
      (node (ref "D232") (pin "1") (pinfunction "A_1") (pintype "passive"))
      (node (ref "S232") (pin "1") (pinfunction "1_1") (pintype "passive"))
    )
    (net (code "54") (name "Net-(D233-A)") (class "Default")
      (node (ref "D233") (pin "1") (pinfunction "A_1") (pintype "passive"))
      (node (ref "S233") (pin "1") (pinfunction "1_1") (pintype "passive"))
    )
    (net (code "55") (name "Net-(D234-A)") (class "Default")
      (node (ref "D234") (pin "1") (pinfunction "A_1") (pintype "passive"))
      (node (ref "S234") (pin "1") (pinfunction "1_1") (pintype "passive"))
    )
    (net (code "56") (name "Net-(D235-A)") (class "Default")
      (node (ref "D235") (pin "1") (pinfunction "A_1") (pintype "passive"))
      (node (ref "S235") (pin "1") (pinfunction "1_1") (pintype "passive"))
    )
    (net (code "57") (name "Net-(D236-A)") (class "Default")
      (node (ref "D236") (pin "1") (pinfunction "A_1") (pintype "passive"))
      (node (ref "S236") (pin "1") (pinfunction "1_1") (pintype "passive"))
    )
    (net (code "58") (name "Net-(D237-A)") (class "Default")
      (node (ref "D237") (pin "1") (pinfunction "A_1") (pintype "passive"))
      (node (ref "S237") (pin "1") (pinfunction "1_1") (pintype "passive"))
    )
    (net (code "59") (name "Net-(D238-A)") (class "Default")
      (node (ref "D238") (pin "1") (pinfunction "A_1") (pintype "passive"))
      (node (ref "S238") (pin "1") (pinfunction "1_1") (pintype "passive"))
    )
    (net (code "60") (name "Net-(D239-A)") (class "Default")
      (node (ref "D239") (pin "1") (pinfunction "A_1") (pintype "passive"))
      (node (ref "S239") (pin "1") (pinfunction "1_1") (pintype "passive"))
    )
    (net (code "61") (name "Net-(D240-A)") (class "Default")
      (node (ref "D240") (pin "1") (pinfunction "A_1") (pintype "passive"))
      (node (ref "S240") (pin "1") (pinfunction "1_1") (pintype "passive"))
    )
    (net (code "62") (name "Net-(D241-A)") (class "Default")
      (node (ref "D241") (pin "1") (pinfunction "A_1") (pintype "passive"))
      (node (ref "S241") (pin "2") (pinfunction "2_2") (pintype "passive"))
    )
    (net (code "63") (name "Net-(D242-A)") (class "Default")
      (node (ref "D242") (pin "1") (pinfunction "A_1") (pintype "passive"))
      (node (ref "S242") (pin "1") (pinfunction "1_1") (pintype "passive"))
      (node (ref "S242_1") (pin "1") (pinfunction "1_1") (pintype "passive"))
    )
    (net (code "64") (name "Net-(D243-A)") (class "Default")
      (node (ref "D243") (pin "1") (pinfunction "A_1") (pintype "passive"))
      (node (ref "S243") (pin "1") (pinfunction "1_1") (pintype "passive"))
    )
    (net (code "65") (name "Net-(D244-A)") (class "Default")
      (node (ref "D244") (pin "1") (pinfunction "A_1") (pintype "passive"))
      (node (ref "S244") (pin "2") (pinfunction "2_2") (pintype "passive"))
    )
    (net (code "66") (name "Net-(D245-A)") (class "Default")
      (node (ref "D245") (pin "1") (pinfunction "A_1") (pintype "passive"))
      (node (ref "S245") (pin "1") (pinfunction "1_1") (pintype "passive"))
    )
    (net (code "67") (name "Net-(D246-A)") (class "Default")
      (node (ref "D246") (pin "1") (pinfunction "A_1") (pintype "passive"))
      (node (ref "S246") (pin "1") (pinfunction "1_1") (pintype "passive"))
    )
    (net (code "68") (name "Net-(D247-A)") (class "Default")
      (node (ref "D247") (pin "1") (pinfunction "A_1") (pintype "passive"))
      (node (ref "S247") (pin "1") (pinfunction "1_1") (pintype "passive"))
    )
    (net (code "69") (name "Net-(D248-A)") (class "Default")
      (node (ref "D248") (pin "1") (pinfunction "A_1") (pintype "passive"))
      (node (ref "S248") (pin "1") (pinfunction "1_1") (pintype "passive"))
    )
    (net (code "70") (name "Net-(D249-A)") (class "Default")
      (node (ref "D249") (pin "1") (pinfunction "A_1") (pintype "passive"))
      (node (ref "S249") (pin "1") (pinfunction "1_1") (pintype "passive"))
    )
    (net (code "71") (name "Net-(D250-A)") (class "Default")
      (node (ref "D250") (pin "1") (pinfunction "A_1") (pintype "passive"))
      (node (ref "S250") (pin "1") (pinfunction "1_1") (pintype "passive"))
    )
    (net (code "72") (name "Net-(D251-A)") (class "Default")
      (node (ref "D251") (pin "1") (pinfunction "A_1") (pintype "passive"))
      (node (ref "S251") (pin "1") (pinfunction "1_1") (pintype "passive"))
    )
    (net (code "73") (name "Net-(D252-A)") (class "Default")
      (node (ref "D252") (pin "1") (pinfunction "A_1") (pintype "passive"))
      (node (ref "S252") (pin "1") (pinfunction "1_1") (pintype "passive"))
    )
    (net (code "74") (name "Net-(D253-A)") (class "Default")
      (node (ref "D253") (pin "1") (pinfunction "A_1") (pintype "passive"))
      (node (ref "S253") (pin "1") (pinfunction "1_1") (pintype "passive"))
    )
    (net (code "75") (name "Net-(D254-A)") (class "Default")
      (node (ref "D254") (pin "1") (pinfunction "A_1") (pintype "passive"))
      (node (ref "S254") (pin "1") (pinfunction "1_1") (pintype "passive"))
    )
    (net (code "76") (name "Net-(D255-A)") (class "Default")
      (node (ref "D255") (pin "1") (pinfunction "A_1") (pintype "passive"))
      (node (ref "S256") (pin "1") (pinfunction "1_1") (pintype "passive"))
    )
    (net (code "77") (name "Net-(D256-A)") (class "Default")
      (node (ref "D256") (pin "1") (pinfunction "A_1") (pintype "passive"))
      (node (ref "S269") (pin "1") (pinfunction "1_1") (pintype "passive"))
    )
    (net (code "78") (name "Net-(D257-A)") (class "Default")
      (node (ref "D257") (pin "1") (pinfunction "A_1") (pintype "passive"))
      (node (ref "S257") (pin "2") (pinfunction "2_2") (pintype "passive"))
    )
    (net (code "79") (name "Net-(D258-A)") (class "Default")
      (node (ref "D258") (pin "1") (pinfunction "A_1") (pintype "passive"))
      (node (ref "S258") (pin "1") (pinfunction "1_1") (pintype "passive"))
    )
    (net (code "80") (name "Net-(D260-A)") (class "Default")
      (node (ref "D260") (pin "1") (pinfunction "A_1") (pintype "passive"))
      (node (ref "S260") (pin "1") (pinfunction "1_1") (pintype "passive"))
    )
    (net (code "81") (name "Net-(D261-A)") (class "Default")
      (node (ref "D261") (pin "1") (pinfunction "A_1") (pintype "passive"))
      (node (ref "S261") (pin "1") (pinfunction "1_1") (pintype "passive"))
      (node (ref "S261_1") (pin "1") (pinfunction "1_1") (pintype "passive"))
    )
    (net (code "82") (name "Net-(D262-A)") (class "Default")
      (node (ref "D262") (pin "1") (pinfunction "A_1") (pintype "passive"))
      (node (ref "S262") (pin "2") (pinfunction "2_2") (pintype "passive"))
      (node (ref "S262_1") (pin "2") (pinfunction "2_2") (pintype "passive"))
    )
    (net (code "83") (name "Net-(D263-A)") (class "Default")
      (node (ref "D263") (pin "1") (pinfunction "A_1") (pintype "passive"))
      (node (ref "S263") (pin "2") (pinfunction "2_2") (pintype "passive"))
      (node (ref "S263_1") (pin "2") (pinfunction "2_2") (pintype "passive"))
    )
    (net (code "84") (name "Net-(D264-A)") (class "Default")
      (node (ref "D264") (pin "1") (pinfunction "A_1") (pintype "passive"))
      (node (ref "S264") (pin "1") (pinfunction "1_1") (pintype "passive"))
      (node (ref "S264_1") (pin "1") (pinfunction "1_1") (pintype "passive"))
    )
    (net (code "85") (name "Net-(D265-A)") (class "Default")
      (node (ref "D265") (pin "1") (pinfunction "A_1") (pintype "passive"))
      (node (ref "S265") (pin "2") (pinfunction "2_2") (pintype "passive"))
      (node (ref "S265_1") (pin "1") (pinfunction "1_1") (pintype "passive"))
    )
    (net (code "86") (name "Net-(D266-A)") (class "Default")
      (node (ref "D266") (pin "1") (pinfunction "A_1") (pintype "passive"))
      (node (ref "S266") (pin "1") (pinfunction "1_1") (pintype "passive"))
    )
    (net (code "87") (name "unconnected-(STAB1-Pad1)") (class "Default")
      (node (ref "STAB1") (pin "1") (pinfunction "1_1") (pintype "passive"))
    )
    (net (code "88") (name "unconnected-(STAB2-Pad1)") (class "Default")
      (node (ref "STAB2") (pin "1") (pinfunction "1_1") (pintype "passive"))
    )
    (net (code "89") (name "unconnected-(STAB3-Pad1)") (class "Default")
      (node (ref "STAB3") (pin "1") (pinfunction "1_1") (pintype "passive"))
    )
  )
)
